# USB_SERIAL_QUAD.net
KiCad netlist of a schematic drawn in Altium Designer
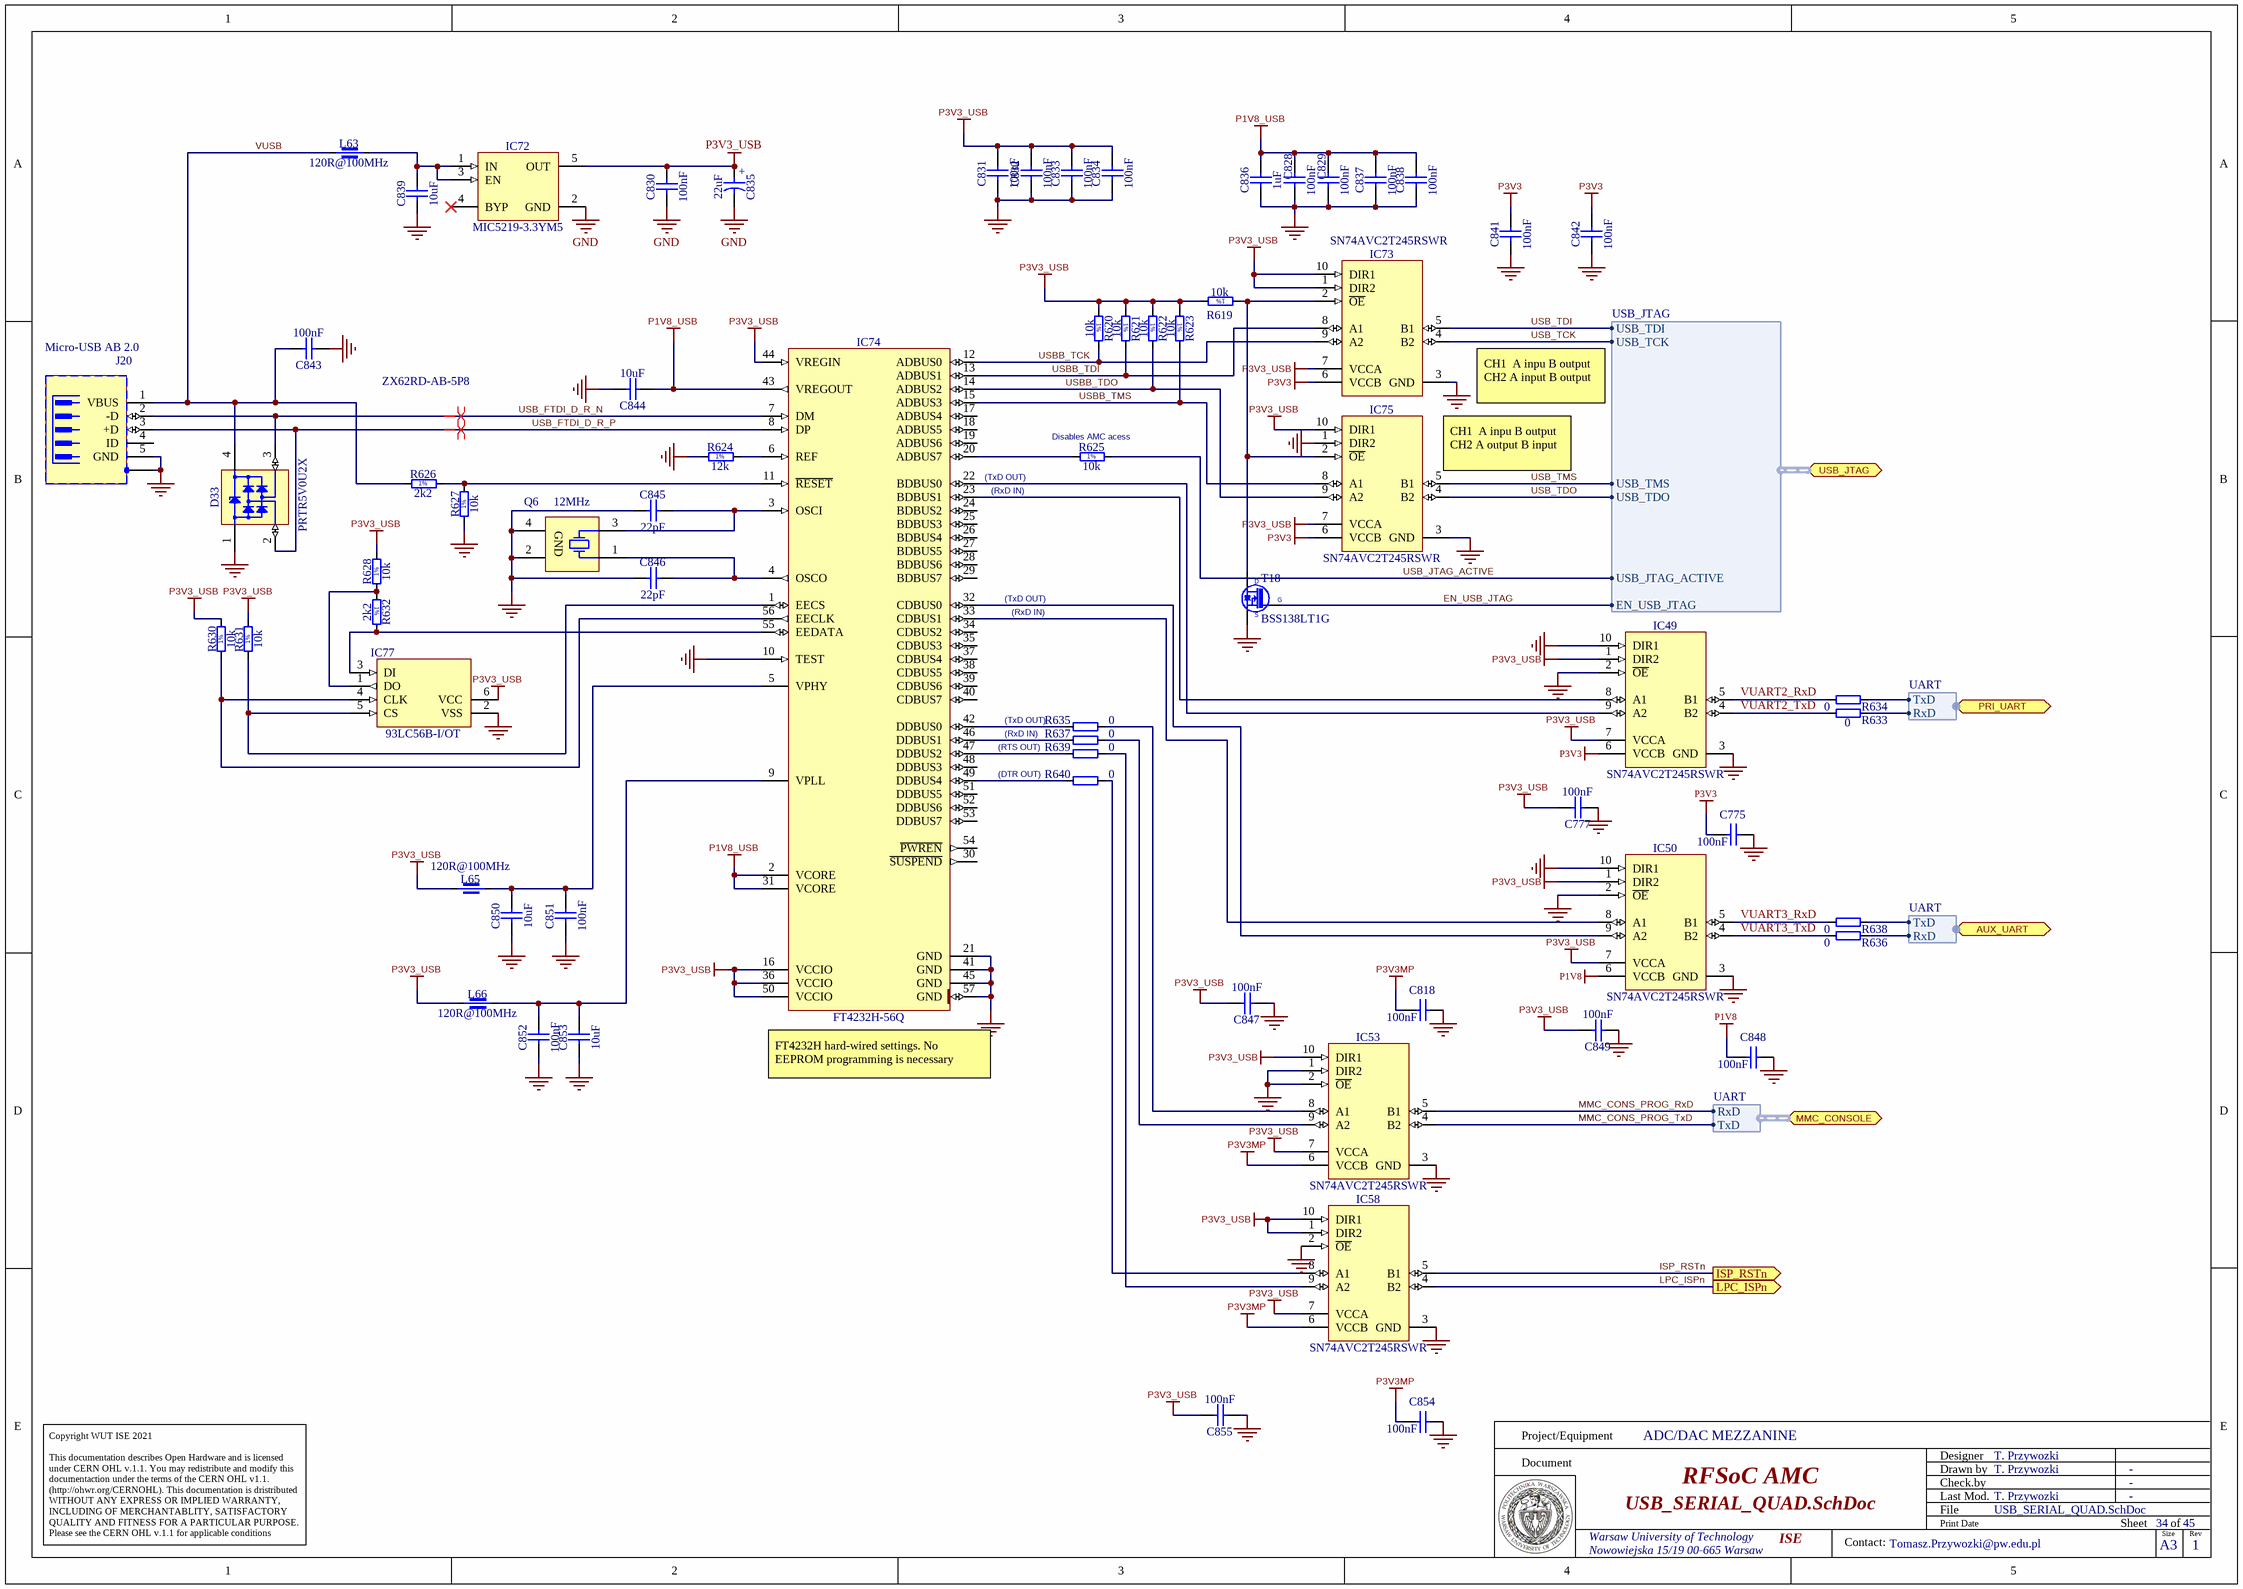
[diagram p0: USB_SERIAL_QUAD.SchDoc]

(export (version "E")
  (design (tool "Eeschema 10.0.6"))
  (components
    (comp (ref "C775")
      (value "100nF")
      (footprint "CAPC0603X33N")
      (description "Non-polarised capacitor")
      (fields
        (field (name "MANUFACTURER PART NUMBER") "CC0201_100NF_6.3V_10%_X5R")
        (field (name "MANUFACTURER") "GENERIC")
        (field (name "AUTHOR") "CERN DEM JLC")
      )
      (libsource (lib "Capacitors") (part "Capacitor - non polarized"))
    )
    (comp (ref "C777")
      (value "100nF")
      (footprint "CAPC0603X33N")
      (description "Non-polarised capacitor")
      (fields
        (field (name "MANUFACTURER PART NUMBER") "CC0201_100NF_6.3V_10%_X5R")
        (field (name "MANUFACTURER") "GENERIC")
        (field (name "AUTHOR") "CERN DEM JLC")
      )
      (libsource (lib "Capacitors") (part "Capacitor - non polarized"))
    )
    (comp (ref "C818")
      (value "100nF")
      (footprint "CAPC0603X33N")
      (description "Non-polarised capacitor")
      (fields
        (field (name "MANUFACTURER PART NUMBER") "CC0201_100NF_6.3V_10%_X5R")
        (field (name "MANUFACTURER") "GENERIC")
        (field (name "AUTHOR") "CERN DEM JLC")
      )
      (libsource (lib "Capacitors") (part "Capacitor - non polarized"))
    )
    (comp (ref "C828")
      (value "100nF")
      (footprint "CAPC0603X33N")
      (description "Non-polarised capacitor")
      (fields
        (field (name "MANUFACTURER PART NUMBER") "CC0201_100NF_6.3V_10%_X5R")
        (field (name "MANUFACTURER") "GENERIC")
        (field (name "AUTHOR") "CERN DEM JLC")
      )
      (libsource (lib "Capacitors") (part "Capacitor - non polarized"))
    )
    (comp (ref "C829")
      (value "100nF")
      (footprint "CAPC0603X33N")
      (description "Non-polarised capacitor")
      (fields
        (field (name "MANUFACTURER PART NUMBER") "CC0201_100NF_6.3V_10%_X5R")
        (field (name "MANUFACTURER") "GENERIC")
        (field (name "AUTHOR") "CERN DEM JLC")
      )
      (libsource (lib "Capacitors") (part "Capacitor - non polarized"))
    )
    (comp (ref "C830")
      (value "100nF")
      (footprint "CAPC0603X33N")
      (description "Non-polarised capacitor")
      (fields
        (field (name "PART NUMBER") "CC0201_100NF_6.3V_10%_X5R")
        (field (name "VOLTAGE") "6.3V")
        (field (name "AUTHOR") "CERN DEM JLC")
      )
      (libsource (lib "Capacitors") (part "Capacitor - non polarized"))
    )
    (comp (ref "C831")
      (value "100nF")
      (footprint "CAPC0603X33N")
      (description "Non-polarised capacitor")
      (fields
        (field (name "MANUFACTURER PART NUMBER") "CC0201_100NF_6.3V_10%_X5R")
        (field (name "MANUFACTURER") "GENERIC")
        (field (name "AUTHOR") "CERN DEM JLC")
      )
      (libsource (lib "Capacitors") (part "Capacitor - non polarized"))
    )
    (comp (ref "C832")
      (value "100nF")
      (footprint "CAPC0603X33N")
      (description "Non-polarised capacitor")
      (fields
        (field (name "MANUFACTURER PART NUMBER") "CC0201_100NF_6.3V_10%_X5R")
        (field (name "MANUFACTURER") "GENERIC")
        (field (name "AUTHOR") "CERN DEM JLC")
      )
      (libsource (lib "Capacitors") (part "Capacitor - non polarized"))
    )
    (comp (ref "C833")
      (value "100nF")
      (footprint "CAPC0603X33N")
      (description "Non-polarised capacitor")
      (fields
        (field (name "MANUFACTURER PART NUMBER") "CC0201_100NF_6.3V_10%_X5R")
        (field (name "MANUFACTURER") "GENERIC")
        (field (name "AUTHOR") "CERN DEM JLC")
      )
      (libsource (lib "Capacitors") (part "Capacitor - non polarized"))
    )
    (comp (ref "C834")
      (value "100nF")
      (footprint "CAPC0603X33N")
      (description "Non-polarised capacitor")
      (fields
        (field (name "MANUFACTURER PART NUMBER") "CC0201_100NF_6.3V_10%_X5R")
        (field (name "MANUFACTURER") "GENERIC")
        (field (name "AUTHOR") "CERN DEM JLC")
      )
      (libsource (lib "Capacitors") (part "Capacitor - non polarized"))
    )
    (comp (ref "C835")
      (value "22uF")
      (footprint "CAPMP3216X180N")
      (description "Polarised capacitor")
      (fields
        (field (name "MANUFACTURER PART NUMBER") "CTE3216-18_22UF_6.3V_10%_LESR0900")
        (field (name "MANUFACTURER") "GENERIC")
        (field (name "AUTHOR") "CERN DEM JLC")
      )
      (libsource (lib "Capacitors") (part "Capacitor - polarized"))
    )
    (comp (ref "C836")
      (value "1uF")
      (footprint "CAPC1005X55N")
      (description "Non-polarised capacitor")
      (fields
        (field (name "MANUFACTURER PART NUMBER") "CC0402_1UF_16V_10%_X5R")
        (field (name "MANUFACTURER") "GENERIC")
        (field (name "AUTHOR") "CERN DEM JLC")
      )
      (libsource (lib "Capacitors") (part "Capacitor - non polarized"))
    )
    (comp (ref "C837")
      (value "100nF")
      (footprint "CAPC0603X33N")
      (description "Non-polarised capacitor")
      (fields
        (field (name "MANUFACTURER PART NUMBER") "CC0201_100NF_6.3V_10%_X5R")
        (field (name "MANUFACTURER") "GENERIC")
        (field (name "AUTHOR") "CERN DEM JLC")
      )
      (libsource (lib "Capacitors") (part "Capacitor - non polarized"))
    )
    (comp (ref "C838")
      (value "100nF")
      (footprint "CAPC0603X33N")
      (description "Non-polarised capacitor")
      (fields
        (field (name "MANUFACTURER PART NUMBER") "CC0201_100NF_6.3V_10%_X5R")
        (field (name "MANUFACTURER") "GENERIC")
        (field (name "AUTHOR") "CERN DEM JLC")
      )
      (libsource (lib "Capacitors") (part "Capacitor - non polarized"))
    )
    (comp (ref "C839")
      (value "10uF")
      (footprint "CAPC1608X87N")
      (description "Non-polarised capacitor")
      (fields
        (field (name "MANUFACTURER PART NUMBER") "CC0603_10uF_6.3V_20%_X5R")
        (field (name "MANUFACTURER") "GENERIC")
        (field (name "AUTHOR") "CERN DEM JLC")
      )
      (libsource (lib "Capacitors") (part "Capacitor - non polarized"))
    )
    (comp (ref "C841")
      (value "100nF")
      (footprint "CAPC0603X33N")
      (description "Non-polarised capacitor")
      (fields
        (field (name "MANUFACTURER PART NUMBER") "CC0201_100NF_6.3V_10%_X5R")
        (field (name "MANUFACTURER") "GENERIC")
        (field (name "AUTHOR") "CERN DEM JLC")
      )
      (libsource (lib "Capacitors") (part "Capacitor - non polarized"))
    )
    (comp (ref "C842")
      (value "100nF")
      (footprint "CAPC0603X33N")
      (description "Non-polarised capacitor")
      (fields
        (field (name "MANUFACTURER PART NUMBER") "CC0201_100NF_6.3V_10%_X5R")
        (field (name "MANUFACTURER") "GENERIC")
        (field (name "AUTHOR") "CERN DEM JLC")
      )
      (libsource (lib "Capacitors") (part "Capacitor - non polarized"))
    )
    (comp (ref "C843")
      (value "100nF")
      (footprint "CAPC0603X33N")
      (description "Non-polarised capacitor")
      (fields
        (field (name "MANUFACTURER PART NUMBER") "CC0201_100NF_6.3V_10%_X5R")
        (field (name "MANUFACTURER") "GENERIC")
        (field (name "AUTHOR") "CERN DEM JLC")
      )
      (libsource (lib "Capacitors") (part "Capacitor - non polarized"))
    )
    (comp (ref "C844")
      (value "10uF")
      (footprint "CAPC1608X87N")
      (description "Non-polarised capacitor")
      (fields
        (field (name "MANUFACTURER PART NUMBER") "CC0603_10uF_6.3V_20%_X5R")
        (field (name "MANUFACTURER") "GENERIC")
        (field (name "AUTHOR") "CERN DEM JLC")
      )
      (libsource (lib "Capacitors") (part "Capacitor - non polarized"))
    )
    (comp (ref "C845")
      (value "22pF")
      (footprint "CAPC1005X55N")
      (description "Non-polarised capacitor")
      (fields
        (field (name "MANUFACTURER PART NUMBER") "CC0402_22PF_50V_5%_C0G")
        (field (name "MANUFACTURER") "GENERIC")
        (field (name "AUTHOR") "CERN DEM JLC")
      )
      (libsource (lib "Capacitors") (part "Capacitor - non polarized"))
    )
    (comp (ref "C846")
      (value "22pF")
      (footprint "CAPC1005X55N")
      (description "Non-polarised capacitor")
      (fields
        (field (name "MANUFACTURER PART NUMBER") "CC0402_22PF_50V_5%_C0G")
        (field (name "MANUFACTURER") "GENERIC")
        (field (name "AUTHOR") "CERN DEM JLC")
      )
      (libsource (lib "Capacitors") (part "Capacitor - non polarized"))
    )
    (comp (ref "C847")
      (value "100nF")
      (footprint "CAPC0603X33N")
      (description "Non-polarised capacitor")
      (fields
        (field (name "MANUFACTURER PART NUMBER") "CC0201_100NF_6.3V_10%_X5R")
        (field (name "MANUFACTURER") "GENERIC")
        (field (name "AUTHOR") "CERN DEM JLC")
      )
      (libsource (lib "Capacitors") (part "Capacitor - non polarized"))
    )
    (comp (ref "C848")
      (value "100nF")
      (footprint "CAPC0603X33N")
      (description "Non-polarised capacitor")
      (fields
        (field (name "MANUFACTURER PART NUMBER") "CC0201_100NF_6.3V_10%_X5R")
        (field (name "MANUFACTURER") "GENERIC")
        (field (name "AUTHOR") "CERN DEM JLC")
      )
      (libsource (lib "Capacitors") (part "Capacitor - non polarized"))
    )
    (comp (ref "C849")
      (value "100nF")
      (footprint "CAPC0603X33N")
      (description "Non-polarised capacitor")
      (fields
        (field (name "MANUFACTURER PART NUMBER") "CC0201_100NF_6.3V_10%_X5R")
        (field (name "MANUFACTURER") "GENERIC")
        (field (name "AUTHOR") "CERN DEM JLC")
      )
      (libsource (lib "Capacitors") (part "Capacitor - non polarized"))
    )
    (comp (ref "C850")
      (value "10uF")
      (footprint "CAPC1608X87N")
      (description "Non-polarised capacitor")
      (fields
        (field (name "MANUFACTURER PART NUMBER") "CC0603_10uF_6.3V_20%_X5R")
        (field (name "MANUFACTURER") "GENERIC")
        (field (name "AUTHOR") "CERN DEM JLC")
      )
      (libsource (lib "Capacitors") (part "Capacitor - non polarized"))
    )
    (comp (ref "C851")
      (value "100nF")
      (footprint "CAPC0603X33N")
      (description "Non-polarised capacitor")
      (fields
        (field (name "MANUFACTURER PART NUMBER") "CC0201_100NF_6.3V_10%_X5R")
        (field (name "MANUFACTURER") "GENERIC")
        (field (name "AUTHOR") "CERN DEM JLC")
      )
      (libsource (lib "Capacitors") (part "Capacitor - non polarized"))
    )
    (comp (ref "C852")
      (value "100nF")
      (footprint "CAPC0603X33N")
      (description "Non-polarised capacitor")
      (fields
        (field (name "MANUFACTURER PART NUMBER") "CC0201_100NF_6.3V_10%_X5R")
        (field (name "MANUFACTURER") "GENERIC")
        (field (name "AUTHOR") "CERN DEM JLC")
      )
      (libsource (lib "Capacitors") (part "Capacitor - non polarized"))
    )
    (comp (ref "C853")
      (value "10uF")
      (footprint "CAPC1608X87N")
      (description "Non-polarised capacitor")
      (fields
        (field (name "MANUFACTURER PART NUMBER") "CC0603_10uF_6.3V_20%_X5R")
        (field (name "MANUFACTURER") "GENERIC")
        (field (name "AUTHOR") "CERN DEM JLC")
      )
      (libsource (lib "Capacitors") (part "Capacitor - non polarized"))
    )
    (comp (ref "C854")
      (value "100nF")
      (footprint "CAPC0603X33N")
      (description "Non-polarised capacitor")
      (fields
        (field (name "MANUFACTURER PART NUMBER") "CC0201_100NF_6.3V_10%_X5R")
        (field (name "MANUFACTURER") "GENERIC")
        (field (name "AUTHOR") "CERN DEM JLC")
      )
      (libsource (lib "Capacitors") (part "Capacitor - non polarized"))
    )
    (comp (ref "C855")
      (value "100nF")
      (footprint "CAPC0603X33N")
      (description "Non-polarised capacitor")
      (fields
        (field (name "MANUFACTURER PART NUMBER") "CC0201_100NF_6.3V_10%_X5R")
        (field (name "MANUFACTURER") "GENERIC")
        (field (name "AUTHOR") "CERN DEM JLC")
      )
      (libsource (lib "Capacitors") (part "Capacitor - non polarized"))
    )
    (comp (ref "D33")
      (value "PRTR5V0U2X")
      (footprint "SOT190P230X110-4N")
      (description "Ultra Low Capacitance Double Rail-to-Rail ESD Protection Diode")
      (fields
        (field (name "MANUFACTURER") "NXP SEMICONDUCTORS")
        (field (name "VOLTAGE") "5.5V")
        (field (name "AUTHOR") "CERN DEM JLC")
      )
      (libsource (lib "ICs And Semiconductors") (part "PRTR5V0U2X"))
    )
    (comp (ref "IC49")
      (value "SN74AVC2T245RSWR")
      (footprint "QFN40P140X180X55-10N")
      (description "Dual-Bit Dual-Supply Bus Transceiver With Configurable Voltage Translation and 3-State Outputs")
      (fields (field (name "MANUFACTURER") "TEXAS INSTRUMENTS") (field (name "AUTHOR") "CERN DEM JLC"))
      (libsource (lib "ICs And Semiconductors") (part "742T245"))
    )
    (comp (ref "IC50")
      (value "SN74AVC2T245RSWR")
      (footprint "QFN40P140X180X55-10N")
      (description "Dual-Bit Dual-Supply Bus Transceiver With Configurable Voltage Translation and 3-State Outputs")
      (fields (field (name "MANUFACTURER") "TEXAS INSTRUMENTS") (field (name "AUTHOR") "CERN DEM JLC"))
      (libsource (lib "ICs And Semiconductors") (part "742T245"))
    )
    (comp (ref "IC53")
      (value "SN74AVC2T245RSWR")
      (footprint "QFN40P140X180X55-10N")
      (description "Dual-Bit Dual-Supply Bus Transceiver With Configurable Voltage Translation and 3-State Outputs")
      (fields (field (name "MANUFACTURER") "TEXAS INSTRUMENTS") (field (name "AUTHOR") "CERN DEM JLC"))
      (libsource (lib "ICs And Semiconductors") (part "742T245"))
    )
    (comp (ref "IC58")
      (value "SN74AVC2T245RSWR")
      (footprint "QFN40P140X180X55-10N")
      (description "Dual-Bit Dual-Supply Bus Transceiver With Configurable Voltage Translation and 3-State Outputs")
      (fields (field (name "MANUFACTURER") "TEXAS INSTRUMENTS") (field (name "AUTHOR") "CERN DEM JLC"))
      (libsource (lib "ICs And Semiconductors") (part "742T245"))
    )
    (comp (ref "IC72")
      (value "MIC5219-3.3YM5")
      (footprint "SOT95P280X145-5N")
      (description "500mA Peak Output LDO Regulator")
      (fields (field (name "MANUFACTURER") "MICROCHIP TECHNOLOGY") (field (name "AUTHOR") "CERN DEM WB"))
      (libsource (lib "ICs And Semiconductors") (part "MIC5219-X.XYM5"))
    )
    (comp (ref "IC73")
      (value "SN74AVC2T245RSWR")
      (footprint "QFN40P140X180X55-10N")
      (description "Dual-Bit Dual-Supply Bus Transceiver With Configurable Voltage Translation and 3-State Outputs")
      (fields (field (name "MANUFACTURER") "TEXAS INSTRUMENTS") (field (name "AUTHOR") "CERN DEM JLC"))
      (libsource (lib "ICs And Semiconductors") (part "742T245"))
    )
    (comp (ref "IC74")
      (value "FT4232H-56Q")
      (footprint "QFN50P800X800X100-57N-S620")
      (description "Quad High Speed USB to Multipurpose UART/MPSSE IC")
      (fields
        (field (name "MANUFACTURER") "FUTURE TECHNOLOGY DEVICES INTERNATIONAL (FTDI)")
        (field (name "AUTHOR") "CERN DEM JLC")
      )
      (libsource (lib "ICs And Semiconductors") (part "FT4232H-56Q"))
    )
    (comp (ref "IC75")
      (value "SN74AVC2T245RSWR")
      (footprint "QFN40P140X180X55-10N")
      (description "Dual-Bit Dual-Supply Bus Transceiver With Configurable Voltage Translation and 3-State Outputs")
      (fields (field (name "MANUFACTURER") "TEXAS INSTRUMENTS") (field (name "AUTHOR") "CERN DEM JLC"))
      (libsource (lib "ICs And Semiconductors") (part "742T245"))
    )
    (comp (ref "IC77")
      (value "93LC56B-I/OT")
      (footprint "SOT95P270x145-6N")
      (description "2K Microwire Compatible Serial EEPROM")
      (fields (field (name "MANUFACTURER") "MICROCHIP TECHNOLOGY") (field (name "AUTHOR") "CERN DEM BC"))
      (libsource (lib "ICs And Semiconductors") (part "93LC56B-I/OT"))
    )
    (comp (ref "J20")
      (value "Micro-USB AB 2.0")
      (footprint "HIROSE_ZX62RD-AB-5P8")
      (description "5 Pin + 1 Shield USB Receptacle")
      (fields
        (field (name "MANUFACTURER PART NUMBER") "ZX62RD-AB-5P8")
        (field (name "MANUFACTURER") "HIROSE (HRS)")
        (field (name "PART NUMBER") "HIROSE_ZX62RD-AB-5P8")
        (field (name "AUTHOR") "CERN DEM JLC")
      )
      (libsource (lib "Connectors") (part "Connector USB 5 Pin + 1Shield"))
    )
    (comp (ref "L63")
      (value "120R@100MHz")
      (footprint "INDC1608X65N")
      (fields
        (field (name "MANUFACTURER PART NUMBER") "BLM18SG121TN1D")
        (field (name "MANUFACTURER") "MURATA")
        (field (name "PART NUMBER") "IND0603_MURATA_BLM18SG121TN1D")
        (field (name "AUTHOR") "CERN DEM JLC")
      )
      (libsource (lib "Inductors & Transformers") (part "Ferrite Bead"))
    )
    (comp (ref "L65")
      (value "120R@100MHz")
      (footprint "INDC1608X65N")
      (fields
        (field (name "MANUFACTURER PART NUMBER") "BLM18SG121TN1D")
        (field (name "MANUFACTURER") "MURATA")
        (field (name "PART NUMBER") "IND0603_MURATA_BLM18SG121TN1D")
        (field (name "AUTHOR") "CERN DEM JLC")
      )
      (libsource (lib "Inductors & Transformers") (part "Ferrite Bead"))
    )
    (comp (ref "L66")
      (value "120R@100MHz")
      (footprint "INDC1608X65N")
      (fields
        (field (name "MANUFACTURER PART NUMBER") "BLM18SG121TN1D")
        (field (name "MANUFACTURER") "MURATA")
        (field (name "PART NUMBER") "IND0603_MURATA_BLM18SG121TN1D")
        (field (name "AUTHOR") "CERN DEM JLC")
      )
      (libsource (lib "Inductors & Transformers") (part "Ferrite Bead"))
    )
    (comp (ref "Q6")
      (value "12MHz")
      (footprint "XTAL_TXC_7M")
      (description "Crystal 4 pins 1=XTAL Control 2=GND3=XTAL 4=GND")
      (fields
        (field (name "MANUFACTURER PART NUMBER") "7M-12.000MAAJ-T")
        (field (name "MANUFACTURER") "TXC CORPORATION")
        (field (name "AUTHOR") "CERN DEM JLC")
      )
      (libsource (lib "ICs And Semiconductors") (part "Quartz Crystal 1X 2GND 3X 4GND"))
    )
    (comp (ref "R619")
      (value "10k")
      (footprint "RESC1005X40N")
      (description "Resistor - 1%")
      (fields
        (field (name "MANUFACTURER PART NUMBER") "R0402_10K_1%_0.0625W_100PPM")
        (field (name "MANUFACTURER") "GENERIC")
        (field (name "AUTHOR") "CERN DEM JLC")
      )
      (libsource (lib "Resistors") (part "Resistor - 1%"))
    )
    (comp (ref "R620")
      (value "10k")
      (footprint "RESC1005X40N")
      (description "Resistor - 1%")
      (fields
        (field (name "MANUFACTURER PART NUMBER") "R0402_10K_1%_0.0625W_100PPM")
        (field (name "MANUFACTURER") "GENERIC")
        (field (name "AUTHOR") "CERN DEM JLC")
      )
      (libsource (lib "Resistors") (part "Resistor - 1%"))
    )
    (comp (ref "R621")
      (value "10k")
      (footprint "RESC1005X40N")
      (description "Resistor - 1%")
      (fields
        (field (name "MANUFACTURER PART NUMBER") "R0402_10K_1%_0.0625W_100PPM")
        (field (name "MANUFACTURER") "GENERIC")
        (field (name "AUTHOR") "CERN DEM JLC")
      )
      (libsource (lib "Resistors") (part "Resistor - 1%"))
    )
    (comp (ref "R622")
      (value "10k")
      (footprint "RESC1005X40N")
      (description "Resistor - 1%")
      (fields
        (field (name "MANUFACTURER PART NUMBER") "R0402_10K_1%_0.0625W_100PPM")
        (field (name "MANUFACTURER") "GENERIC")
        (field (name "AUTHOR") "CERN DEM JLC")
      )
      (libsource (lib "Resistors") (part "Resistor - 1%"))
    )
    (comp (ref "R623")
      (value "10k")
      (footprint "RESC1005X40N")
      (description "Resistor - 1%")
      (fields
        (field (name "MANUFACTURER PART NUMBER") "R0402_10K_1%_0.0625W_100PPM")
        (field (name "MANUFACTURER") "GENERIC")
        (field (name "AUTHOR") "CERN DEM JLC")
      )
      (libsource (lib "Resistors") (part "Resistor - 1%"))
    )
    (comp (ref "R624")
      (value "12k")
      (footprint "RESC1005X40N")
      (description "Resistor - 1%")
      (fields
        (field (name "MANUFACTURER PART NUMBER") "R0402_12K_1%_0.0625W_100PPM")
        (field (name "MANUFACTURER") "GENERIC")
        (field (name "AUTHOR") "CERN DEM JLC")
      )
      (libsource (lib "Resistors") (part "Resistor - 1%"))
    )
    (comp (ref "R625")
      (value "10k")
      (footprint "RESC1005X40N")
      (description "Resistor - 1%")
      (fields
        (field (name "MANUFACTURER PART NUMBER") "R0402_10K_1%_0.0625W_100PPM")
        (field (name "MANUFACTURER") "GENERIC")
        (field (name "AUTHOR") "CERN DEM JLC")
      )
      (libsource (lib "Resistors") (part "Resistor - 1%"))
    )
    (comp (ref "R626")
      (value "2k2")
      (footprint "RESC1005X40N")
      (description "Resistor - 1%")
      (fields
        (field (name "MANUFACTURER PART NUMBER") "R0402_2K2_1%_0.0625W_100PPM")
        (field (name "MANUFACTURER") "GENERIC")
        (field (name "AUTHOR") "CERN DEM JLC")
      )
      (libsource (lib "Resistors") (part "Resistor - 1%"))
    )
    (comp (ref "R627")
      (value "10k")
      (footprint "RESC1005X40N")
      (description "Resistor - 1%")
      (fields
        (field (name "MANUFACTURER PART NUMBER") "R0402_10K_1%_0.0625W_100PPM")
        (field (name "MANUFACTURER") "GENERIC")
        (field (name "AUTHOR") "CERN DEM JLC")
      )
      (libsource (lib "Resistors") (part "Resistor - 1%"))
    )
    (comp (ref "R628")
      (value "10k")
      (footprint "RESC1005X40N")
      (description "Resistor - 1%")
      (fields
        (field (name "MANUFACTURER PART NUMBER") "R0402_10K_1%_0.0625W_100PPM")
        (field (name "MANUFACTURER") "GENERIC")
        (field (name "AUTHOR") "CERN DEM JLC")
      )
      (libsource (lib "Resistors") (part "Resistor - 1%"))
    )
    (comp (ref "R630")
      (value "10k")
      (footprint "RESC1005X40N")
      (description "Resistor - 1%")
      (fields
        (field (name "MANUFACTURER PART NUMBER") "R0402_10K_1%_0.0625W_100PPM")
        (field (name "MANUFACTURER") "GENERIC")
        (field (name "AUTHOR") "CERN DEM JLC")
      )
      (libsource (lib "Resistors") (part "Resistor - 1%"))
    )
    (comp (ref "R631")
      (value "10k")
      (footprint "RESC1005X40N")
      (description "Resistor - 1%")
      (fields
        (field (name "MANUFACTURER PART NUMBER") "R0402_10K_1%_0.0625W_100PPM")
        (field (name "MANUFACTURER") "GENERIC")
        (field (name "AUTHOR") "CERN DEM JLC")
      )
      (libsource (lib "Resistors") (part "Resistor - 1%"))
    )
    (comp (ref "R632")
      (value "2k2")
      (footprint "RESC1005X40N")
      (description "Resistor - 1%")
      (fields
        (field (name "MANUFACTURER PART NUMBER") "R0402_2K2_1%_0.0625W_100PPM")
        (field (name "MANUFACTURER") "GENERIC")
        (field (name "AUTHOR") "CERN DEM JLC")
      )
      (libsource (lib "Resistors") (part "Resistor - 1%"))
    )
    (comp (ref "R633")
      (value "0")
      (footprint "RESC1005X40N")
      (description "Resistor")
      (fields
        (field (name "MANUFACTURER PART NUMBER") "R0402_0R_JUMPER")
        (field (name "MANUFACTURER") "GENERIC")
        (field (name "AUTHOR") "CERN DEM JLC")
      )
      (libsource (lib "Resistors") (part "Resistor"))
    )
    (comp (ref "R634")
      (value "0")
      (footprint "RESC1005X40N")
      (description "Resistor")
      (fields
        (field (name "MANUFACTURER PART NUMBER") "R0402_0R_JUMPER")
        (field (name "MANUFACTURER") "GENERIC")
        (field (name "AUTHOR") "CERN DEM JLC")
      )
      (libsource (lib "Resistors") (part "Resistor"))
    )
    (comp (ref "R635")
      (value "0")
      (footprint "RESC1005X40N")
      (description "Resistor")
      (fields
        (field (name "MANUFACTURER PART NUMBER") "R0402_0R_JUMPER")
        (field (name "MANUFACTURER") "GENERIC")
        (field (name "AUTHOR") "CERN DEM JLC")
      )
      (libsource (lib "Resistors") (part "Resistor"))
    )
    (comp (ref "R636")
      (value "0")
      (footprint "RESC1005X40N")
      (description "Resistor")
      (fields
        (field (name "MANUFACTURER PART NUMBER") "R0402_0R_JUMPER")
        (field (name "MANUFACTURER") "GENERIC")
        (field (name "AUTHOR") "CERN DEM JLC")
      )
      (libsource (lib "Resistors") (part "Resistor"))
    )
    (comp (ref "R637")
      (value "0")
      (footprint "RESC1005X40N")
      (description "Resistor")
      (fields
        (field (name "MANUFACTURER PART NUMBER") "R0402_0R_JUMPER")
        (field (name "MANUFACTURER") "GENERIC")
        (field (name "AUTHOR") "CERN DEM JLC")
      )
      (libsource (lib "Resistors") (part "Resistor"))
    )
    (comp (ref "R638")
      (value "0")
      (footprint "RESC1005X40N")
      (description "Resistor")
      (fields
        (field (name "MANUFACTURER PART NUMBER") "R0402_0R_JUMPER")
        (field (name "MANUFACTURER") "GENERIC")
        (field (name "AUTHOR") "CERN DEM JLC")
      )
      (libsource (lib "Resistors") (part "Resistor"))
    )
    (comp (ref "R639")
      (value "0")
      (footprint "RESC1005X40N")
      (description "Resistor")
      (fields
        (field (name "MANUFACTURER PART NUMBER") "R0402_0R_JUMPER")
        (field (name "MANUFACTURER") "GENERIC")
        (field (name "AUTHOR") "CERN DEM JLC")
      )
      (libsource (lib "Resistors") (part "Resistor"))
    )
    (comp (ref "R640")
      (value "0")
      (footprint "RESC1005X40N")
      (description "Resistor")
      (fields
        (field (name "MANUFACTURER PART NUMBER") "R0402_0R_JUMPER")
        (field (name "MANUFACTURER") "GENERIC")
        (field (name "AUTHOR") "CERN DEM JLC")
      )
      (libsource (lib "Resistors") (part "Resistor"))
    )
    (comp (ref "T18")
      (value "BSS138LT1G")
      (footprint "SOT95P240X110-3N")
      (description "N-CHANNEL MOSFET WITH DIODE")
      (fields (field (name "MANUFACTURER") "ON SEMICONDUCTOR") (field (name "AUTHOR") "CERN DEM JLC"))
      (libsource (lib "ICs And Semiconductors") (part "N-MOSFET-D 1G 2S 3D"))
    )
  )
  (nets
    (net (code "3") (name "/EN_USB_JTAG") (class "Default")
      (node (ref "T18") (pin "1") (pinfunction "G_1") (pintype "passive"))
    )
    (net (code "4") (name "/ISP_RSTn") (class "Default")
      (node (ref "IC58") (pin "5") (pinfunction "B1_5") (pintype "bidirectional"))
    )
    (net (code "5") (name "/LPC_ISPn") (class "Default")
      (node (ref "IC58") (pin "4") (pinfunction "B2_4") (pintype "bidirectional"))
    )
    (net (code "6") (name "/MMC_CONS_PROG_RxD") (class "Default")
      (node (ref "IC53") (pin "5") (pinfunction "B1_5") (pintype "bidirectional"))
    )
    (net (code "7") (name "/MMC_CONS_PROG_TxD") (class "Default")
      (node (ref "IC53") (pin "4") (pinfunction "B2_4") (pintype "bidirectional"))
    )
    (net (code "8") (name "/USBB_TCK") (class "Default")
      (node (ref "IC73") (pin "9") (pinfunction "A2_9") (pintype "bidirectional"))
      (node (ref "IC74") (pin "12") (pinfunction "ADBUS0_12") (pintype "bidirectional"))
      (node (ref "R620") (pin "2") (pinfunction "2_2") (pintype "passive"))
    )
    (net (code "9") (name "/USBB_TDI") (class "Default")
      (node (ref "IC73") (pin "8") (pinfunction "A1_8") (pintype "bidirectional"))
      (node (ref "IC74") (pin "13") (pinfunction "ADBUS1_13") (pintype "bidirectional"))
      (node (ref "R621") (pin "2") (pinfunction "2_2") (pintype "passive"))
    )
    (net (code "10") (name "/USBB_TDO") (class "Default")
      (node (ref "IC74") (pin "14") (pinfunction "ADBUS2_14") (pintype "bidirectional"))
      (node (ref "IC75") (pin "9") (pinfunction "A2_9") (pintype "bidirectional"))
      (node (ref "R622") (pin "2") (pinfunction "2_2") (pintype "passive"))
    )
    (net (code "11") (name "/USBB_TMS") (class "Default")
      (node (ref "IC74") (pin "15") (pinfunction "ADBUS3_15") (pintype "bidirectional"))
      (node (ref "IC75") (pin "8") (pinfunction "A1_8") (pintype "bidirectional"))
      (node (ref "R623") (pin "2") (pinfunction "2_2") (pintype "passive"))
    )
    (net (code "12") (name "/USB_FTDI_D_R_N") (class "Default")
      (node (ref "D33") (pin "3") (pinfunction "I/O2_3") (pintype "bidirectional"))
      (node (ref "IC74") (pin "7") (pinfunction "DM_7") (pintype "input"))
      (node (ref "J20") (pin "2") (pinfunction "-D_2") (pintype "bidirectional"))
    )
    (net (code "13") (name "/USB_FTDI_D_R_P") (class "Default")
      (node (ref "D33") (pin "2") (pinfunction "I/O1_2") (pintype "bidirectional"))
      (node (ref "IC74") (pin "8") (pinfunction "DP_8") (pintype "input"))
      (node (ref "J20") (pin "3") (pinfunction "+D_3") (pintype "bidirectional"))
    )
    (net (code "14") (name "/USB_JTAG_ACTIVE") (class "Default")
      (node (ref "R625") (pin "2") (pinfunction "2_2") (pintype "passive"))
    )
    (net (code "15") (name "/USB_TCK") (class "Default")
      (node (ref "IC73") (pin "4") (pinfunction "B2_4") (pintype "bidirectional"))
    )
    (net (code "16") (name "/USB_TDI") (class "Default")
      (node (ref "IC73") (pin "5") (pinfunction "B1_5") (pintype "bidirectional"))
    )
    (net (code "17") (name "/USB_TDO") (class "Default")
      (node (ref "IC75") (pin "4") (pinfunction "B2_4") (pintype "bidirectional"))
    )
    (net (code "18") (name "/USB_TMS") (class "Default")
      (node (ref "IC75") (pin "5") (pinfunction "B1_5") (pintype "bidirectional"))
    )
    (net (code "19") (name "/VUART2_RxD") (class "Default")
      (node (ref "IC49") (pin "5") (pinfunction "B1_5") (pintype "bidirectional"))
      (node (ref "R634") (pin "2") (pinfunction "2_2") (pintype "passive"))
    )
    (net (code "20") (name "/VUART2_TxD") (class "Default")
      (node (ref "IC49") (pin "4") (pinfunction "B2_4") (pintype "bidirectional"))
      (node (ref "R633") (pin "2") (pinfunction "2_2") (pintype "passive"))
    )
    (net (code "21") (name "/VUART3_RxD") (class "Default")
      (node (ref "IC50") (pin "5") (pinfunction "B1_5") (pintype "bidirectional"))
      (node (ref "R638") (pin "2") (pinfunction "2_2") (pintype "passive"))
    )
    (net (code "22") (name "/VUART3_TxD") (class "Default")
      (node (ref "IC50") (pin "4") (pinfunction "B2_4") (pintype "bidirectional"))
      (node (ref "R636") (pin "2") (pinfunction "2_2") (pintype "passive"))
    )
    (net (code "23") (name "/VUSB") (class "Default")
      (node (ref "C843") (pin "2") (pinfunction "2_2") (pintype "passive"))
      (node (ref "D33") (pin "4") (pinfunction "VCC_4") (pintype "power_in"))
      (node (ref "J20") (pin "1") (pinfunction "VBUS_1") (pintype "power_in"))
      (node (ref "L63") (pin "1") (pinfunction "1_1") (pintype "passive"))
      (node (ref "R626") (pin "1") (pinfunction "1_1") (pintype "passive"))
    )
    (net (code "26") (name "GND") (class "Default")
      (node (ref "C775") (pin "1") (pinfunction "1_1") (pintype "passive"))
      (node (ref "C777") (pin "1") (pinfunction "1_1") (pintype "passive"))
      (node (ref "C818") (pin "1") (pinfunction "1_1") (pintype "passive"))
      (node (ref "C828") (pin "1") (pinfunction "1_1") (pintype "passive"))
      (node (ref "C829") (pin "1") (pinfunction "1_1") (pintype "passive"))
      (node (ref "C830") (pin "1") (pinfunction "1_1") (pintype "passive"))
      (node (ref "C831") (pin "1") (pinfunction "1_1") (pintype "passive"))
      (node (ref "C832") (pin "1") (pinfunction "1_1") (pintype "passive"))
      (node (ref "C833") (pin "1") (pinfunction "1_1") (pintype "passive"))
      (node (ref "C834") (pin "1") (pinfunction "1_1") (pintype "passive"))
      (node (ref "C835") (pin "2") (pinfunction "2_2") (pintype "passive"))
      (node (ref "C836") (pin "2") (pinfunction "2_2") (pintype "passive"))
      (node (ref "C837") (pin "1") (pinfunction "1_1") (pintype "passive"))
      (node (ref "C838") (pin "1") (pinfunction "1_1") (pintype "passive"))
      (node (ref "C839") (pin "1") (pinfunction "1_1") (pintype "passive"))
      (node (ref "C841") (pin "1") (pinfunction "1_1") (pintype "passive"))
      (node (ref "C842") (pin "1") (pinfunction "1_1") (pintype "passive"))
      (node (ref "C843") (pin "1") (pinfunction "1_1") (pintype "passive"))
      (node (ref "C844") (pin "2") (pinfunction "2_2") (pintype "passive"))
      (node (ref "C845") (pin "1") (pinfunction "1_1") (pintype "passive"))
      (node (ref "C846") (pin "1") (pinfunction "1_1") (pintype "passive"))
      (node (ref "C847") (pin "1") (pinfunction "1_1") (pintype "passive"))
      (node (ref "C848") (pin "1") (pinfunction "1_1") (pintype "passive"))
      (node (ref "C849") (pin "1") (pinfunction "1_1") (pintype "passive"))
      (node (ref "C850") (pin "1") (pinfunction "1_1") (pintype "passive"))
      (node (ref "C851") (pin "1") (pinfunction "1_1") (pintype "passive"))
      (node (ref "C852") (pin "1") (pinfunction "1_1") (pintype "passive"))
      (node (ref "C853") (pin "1") (pinfunction "1_1") (pintype "passive"))
      (node (ref "C854") (pin "1") (pinfunction "1_1") (pintype "passive"))
      (node (ref "C855") (pin "1") (pinfunction "1_1") (pintype "passive"))
      (node (ref "D33") (pin "1") (pinfunction "GND_1") (pintype "power_in"))
      (node (ref "IC49") (pin "10") (pinfunction "DIR1_10") (pintype "input"))
      (node (ref "IC49") (pin "2") (pinfunction "~{OE}_2") (pintype "input"))
      (node (ref "IC49") (pin "3") (pinfunction "GND_3") (pintype "power_in"))
      (node (ref "IC50") (pin "10") (pinfunction "DIR1_10") (pintype "input"))
      (node (ref "IC50") (pin "2") (pinfunction "~{OE}_2") (pintype "input"))
      (node (ref "IC50") (pin "3") (pinfunction "GND_3") (pintype "power_in"))
      (node (ref "IC53") (pin "1") (pinfunction "DIR2_1") (pintype "input"))
      (node (ref "IC53") (pin "2") (pinfunction "~{OE}_2") (pintype "input"))
      (node (ref "IC53") (pin "3") (pinfunction "GND_3") (pintype "power_in"))
      (node (ref "IC58") (pin "2") (pinfunction "~{OE}_2") (pintype "input"))
      (node (ref "IC58") (pin "3") (pinfunction "GND_3") (pintype "power_in"))
      (node (ref "IC72") (pin "2") (pinfunction "GND_2") (pintype "power_in"))
      (node (ref "IC73") (pin "3") (pinfunction "GND_3") (pintype "power_in"))
      (node (ref "IC74") (pin "10") (pinfunction "TEST_10") (pintype "input"))
      (node (ref "IC74") (pin "21") (pinfunction "GND_21") (pintype "power_in"))
      (node (ref "IC74") (pin "41") (pinfunction "GND_41") (pintype "power_in"))
      (node (ref "IC74") (pin "45") (pinfunction "GND_45") (pintype "power_in"))
      (node (ref "IC74") (pin "57") (pinfunction "GND_57") (pintype "bidirectional"))
      (node (ref "IC75") (pin "1") (pinfunction "DIR2_1") (pintype "input"))
      (node (ref "IC75") (pin "3") (pinfunction "GND_3") (pintype "power_in"))
      (node (ref "IC77") (pin "2") (pinfunction "VSS_2") (pintype "power_in"))
      (node (ref "J20") (pin "5") (pinfunction "GND_5") (pintype "power_in"))
      (node (ref "J20") (pin "6") (pinfunction "SH_6") (pintype "power_in"))
      (node (ref "Q6") (pin "2") (pinfunction "GND_2") (pintype "power_in"))
      (node (ref "Q6") (pin "4") (pinfunction "GND_4") (pintype "power_in"))
      (node (ref "R624") (pin "1") (pinfunction "1_1") (pintype "passive"))
      (node (ref "R627") (pin "1") (pinfunction "1_1") (pintype "passive"))
      (node (ref "T18") (pin "2") (pinfunction "S_2") (pintype "passive"))
    )
    (net (code "27") (name "Net-(IC49-A1)") (class "Default")
      (node (ref "IC49") (pin "8") (pinfunction "A1_8") (pintype "bidirectional"))
      (node (ref "IC74") (pin "23") (pinfunction "BDBUS1_23") (pintype "bidirectional"))
    )
    (net (code "28") (name "Net-(IC49-A2)") (class "Default")
      (node (ref "IC49") (pin "9") (pinfunction "A2_9") (pintype "bidirectional"))
      (node (ref "IC74") (pin "22") (pinfunction "BDBUS0_22") (pintype "bidirectional"))
    )
    (net (code "29") (name "Net-(IC50-A1)") (class "Default")
      (node (ref "IC50") (pin "8") (pinfunction "A1_8") (pintype "bidirectional"))
      (node (ref "IC74") (pin "33") (pinfunction "CDBUS1_33") (pintype "bidirectional"))
    )
    (net (code "30") (name "Net-(IC50-A2)") (class "Default")
      (node (ref "IC50") (pin "9") (pinfunction "A2_9") (pintype "bidirectional"))
      (node (ref "IC74") (pin "32") (pinfunction "CDBUS0_32") (pintype "bidirectional"))
    )
    (net (code "31") (name "Net-(IC53-A1)") (class "Default")
      (node (ref "IC53") (pin "8") (pinfunction "A1_8") (pintype "bidirectional"))
      (node (ref "R635") (pin "2") (pinfunction "2_2") (pintype "passive"))
    )
    (net (code "32") (name "Net-(IC53-A2)") (class "Default")
      (node (ref "IC53") (pin "9") (pinfunction "A2_9") (pintype "bidirectional"))
      (node (ref "R637") (pin "2") (pinfunction "2_2") (pintype "passive"))
    )
    (net (code "33") (name "Net-(IC58-A1)") (class "Default")
      (node (ref "IC58") (pin "8") (pinfunction "A1_8") (pintype "bidirectional"))
      (node (ref "R640") (pin "2") (pinfunction "2_2") (pintype "passive"))
    )
    (net (code "34") (name "Net-(IC58-A2)") (class "Default")
      (node (ref "IC58") (pin "9") (pinfunction "A2_9") (pintype "bidirectional"))
      (node (ref "R639") (pin "2") (pinfunction "2_2") (pintype "passive"))
    )
    (net (code "35") (name "Net-(IC72-EN)") (class "Default")
      (node (ref "C839") (pin "2") (pinfunction "2_2") (pintype "passive"))
      (node (ref "IC72") (pin "1") (pinfunction "IN_1") (pintype "input"))
      (node (ref "IC72") (pin "3") (pinfunction "EN_3") (pintype "input"))
      (node (ref "L63") (pin "2") (pinfunction "2_2") (pintype "passive"))
    )
    (net (code "36") (name "Net-(IC73-~{OE})") (class "Default")
      (node (ref "IC73") (pin "2") (pinfunction "~{OE}_2") (pintype "input"))
      (node (ref "IC75") (pin "2") (pinfunction "~{OE}_2") (pintype "input"))
      (node (ref "R619") (pin "1") (pinfunction "1_1") (pintype "passive"))
      (node (ref "T18") (pin "3") (pinfunction "D_3") (pintype "passive"))
    )
    (net (code "37") (name "Net-(IC74-ADBUS7)") (class "Default")
      (node (ref "IC74") (pin "20") (pinfunction "ADBUS7_20") (pintype "bidirectional"))
      (node (ref "R625") (pin "1") (pinfunction "1_1") (pintype "passive"))
    )
    (net (code "38") (name "Net-(IC74-DDBUS0)") (class "Default")
      (node (ref "IC74") (pin "42") (pinfunction "DDBUS0_42") (pintype "bidirectional"))
      (node (ref "R635") (pin "1") (pinfunction "1_1") (pintype "passive"))
    )
    (net (code "39") (name "Net-(IC74-DDBUS1)") (class "Default")
      (node (ref "IC74") (pin "46") (pinfunction "DDBUS1_46") (pintype "bidirectional"))
      (node (ref "R637") (pin "1") (pinfunction "1_1") (pintype "passive"))
    )
    (net (code "40") (name "Net-(IC74-DDBUS2)") (class "Default")
      (node (ref "IC74") (pin "47") (pinfunction "DDBUS2_47") (pintype "bidirectional"))
      (node (ref "R639") (pin "1") (pinfunction "1_1") (pintype "passive"))
    )
    (net (code "41") (name "Net-(IC74-DDBUS4)") (class "Default")
      (node (ref "IC74") (pin "49") (pinfunction "DDBUS4_49") (pintype "bidirectional"))
      (node (ref "R640") (pin "1") (pinfunction "1_1") (pintype "passive"))
    )
    (net (code "42") (name "Net-(IC74-EECLK)") (class "Default")
      (node (ref "IC74") (pin "56") (pinfunction "EECLK_56") (pintype "output"))
      (node (ref "IC77") (pin "4") (pinfunction "CLK_4") (pintype "input"))
      (node (ref "R630") (pin "1") (pinfunction "1_1") (pintype "passive"))
    )
    (net (code "43") (name "Net-(IC74-EECS)") (class "Default")
      (node (ref "IC74") (pin "1") (pinfunction "EECS_1") (pintype "bidirectional"))
      (node (ref "IC77") (pin "5") (pinfunction "CS_5") (pintype "input"))
      (node (ref "R631") (pin "1") (pinfunction "1_1") (pintype "passive"))
    )
    (net (code "44") (name "Net-(IC74-EEDATA)") (class "Default")
      (node (ref "IC74") (pin "55") (pinfunction "EEDATA_55") (pintype "bidirectional"))
      (node (ref "IC77") (pin "3") (pinfunction "DI_3") (pintype "input"))
      (node (ref "R632") (pin "2") (pinfunction "2_2") (pintype "passive"))
    )
    (net (code "45") (name "Net-(IC74-OSCI)") (class "Default")
      (node (ref "C845") (pin "2") (pinfunction "2_2") (pintype "passive"))
      (node (ref "IC74") (pin "3") (pinfunction "OSCI_3") (pintype "input"))
      (node (ref "Q6") (pin "3") (pinfunction "X_3") (pintype "passive"))
    )
    (net (code "46") (name "Net-(IC74-OSCO)") (class "Default")
      (node (ref "C846") (pin "2") (pinfunction "2_2") (pintype "passive"))
      (node (ref "IC74") (pin "4") (pinfunction "OSCO_4") (pintype "output"))
      (node (ref "Q6") (pin "1") (pinfunction "X_1") (pintype "passive"))
    )
    (net (code "47") (name "Net-(IC74-REF)") (class "Default")
      (node (ref "IC74") (pin "6") (pinfunction "REF_6") (pintype "input"))
      (node (ref "R624") (pin "2") (pinfunction "2_2") (pintype "passive"))
    )
    (net (code "48") (name "Net-(IC74-VPHY)") (class "Default")
      (node (ref "C850") (pin "2") (pinfunction "2_2") (pintype "passive"))
      (node (ref "C851") (pin "2") (pinfunction "2_2") (pintype "passive"))
      (node (ref "IC74") (pin "5") (pinfunction "VPHY_5") (pintype "power_in"))
      (node (ref "L65") (pin "2") (pinfunction "2_2") (pintype "passive"))
    )
    (net (code "49") (name "Net-(IC74-VPLL)") (class "Default")
      (node (ref "C852") (pin "2") (pinfunction "2_2") (pintype "passive"))
      (node (ref "C853") (pin "2") (pinfunction "2_2") (pintype "passive"))
      (node (ref "IC74") (pin "9") (pinfunction "VPLL_9") (pintype "power_in"))
      (node (ref "L66") (pin "2") (pinfunction "2_2") (pintype "passive"))
    )
    (net (code "50") (name "Net-(IC74-~{RESET})") (class "Default")
      (node (ref "IC74") (pin "11") (pinfunction "~{RESET}_11") (pintype "input"))
      (node (ref "R626") (pin "2") (pinfunction "2_2") (pintype "passive"))
      (node (ref "R627") (pin "2") (pinfunction "2_2") (pintype "passive"))
    )
    (net (code "51") (name "Net-(IC77-DO)") (class "Default")
      (node (ref "IC77") (pin "1") (pinfunction "DO_1") (pintype "output"))
      (node (ref "R628") (pin "1") (pinfunction "1_1") (pintype "passive"))
      (node (ref "R632") (pin "1") (pinfunction "1_1") (pintype "passive"))
    )
    (net (code "52") (name "P1V8") (class "Default")
      (node (ref "C848") (pin "2") (pinfunction "2_2") (pintype "passive"))
      (node (ref "IC50") (pin "6") (pinfunction "VCCB_6") (pintype "power_in"))
    )
    (net (code "53") (name "P1V8_USB") (class "Default")
      (node (ref "C828") (pin "2") (pinfunction "2_2") (pintype "passive"))
      (node (ref "C829") (pin "2") (pinfunction "2_2") (pintype "passive"))
      (node (ref "C836") (pin "1") (pinfunction "1_1") (pintype "passive"))
      (node (ref "C837") (pin "2") (pinfunction "2_2") (pintype "passive"))
      (node (ref "C838") (pin "2") (pinfunction "2_2") (pintype "passive"))
      (node (ref "C844") (pin "1") (pinfunction "1_1") (pintype "passive"))
      (node (ref "IC74") (pin "2") (pinfunction "VCORE_2") (pintype "power_in"))
      (node (ref "IC74") (pin "31") (pinfunction "VCORE_31") (pintype "power_in"))
      (node (ref "IC74") (pin "43") (pinfunction "VREGOUT_43") (pintype "output"))
    )
    (net (code "54") (name "P3V3") (class "Default")
      (node (ref "C775") (pin "2") (pinfunction "2_2") (pintype "passive"))
      (node (ref "C841") (pin "2") (pinfunction "2_2") (pintype "passive"))
      (node (ref "C842") (pin "2") (pinfunction "2_2") (pintype "passive"))
      (node (ref "IC49") (pin "6") (pinfunction "VCCB_6") (pintype "power_in"))
      (node (ref "IC73") (pin "6") (pinfunction "VCCB_6") (pintype "power_in"))
      (node (ref "IC75") (pin "6") (pinfunction "VCCB_6") (pintype "power_in"))
    )
    (net (code "55") (name "P3V3MP") (class "Default")
      (node (ref "C818") (pin "2") (pinfunction "2_2") (pintype "passive"))
      (node (ref "C854") (pin "2") (pinfunction "2_2") (pintype "passive"))
      (node (ref "IC53") (pin "6") (pinfunction "VCCB_6") (pintype "power_in"))
      (node (ref "IC58") (pin "6") (pinfunction "VCCB_6") (pintype "power_in"))
    )
    (net (code "56") (name "P3V3_USB") (class "Default")
      (node (ref "C777") (pin "2") (pinfunction "2_2") (pintype "passive"))
      (node (ref "C830") (pin "2") (pinfunction "2_2") (pintype "passive"))
      (node (ref "C831") (pin "2") (pinfunction "2_2") (pintype "passive"))
      (node (ref "C832") (pin "2") (pinfunction "2_2") (pintype "passive"))
      (node (ref "C833") (pin "2") (pinfunction "2_2") (pintype "passive"))
      (node (ref "C834") (pin "2") (pinfunction "2_2") (pintype "passive"))
      (node (ref "C835") (pin "1") (pinfunction "1_1") (pintype "passive"))
      (node (ref "C847") (pin "2") (pinfunction "2_2") (pintype "passive"))
      (node (ref "C849") (pin "2") (pinfunction "2_2") (pintype "passive"))
      (node (ref "C855") (pin "2") (pinfunction "2_2") (pintype "passive"))
      (node (ref "IC49") (pin "1") (pinfunction "DIR2_1") (pintype "input"))
      (node (ref "IC49") (pin "7") (pinfunction "VCCA_7") (pintype "power_in"))
      (node (ref "IC50") (pin "1") (pinfunction "DIR2_1") (pintype "input"))
      (node (ref "IC50") (pin "7") (pinfunction "VCCA_7") (pintype "power_in"))
      (node (ref "IC53") (pin "10") (pinfunction "DIR1_10") (pintype "input"))
      (node (ref "IC53") (pin "7") (pinfunction "VCCA_7") (pintype "power_in"))
      (node (ref "IC58") (pin "1") (pinfunction "DIR2_1") (pintype "input"))
      (node (ref "IC58") (pin "10") (pinfunction "DIR1_10") (pintype "input"))
      (node (ref "IC58") (pin "7") (pinfunction "VCCA_7") (pintype "power_in"))
      (node (ref "IC72") (pin "5") (pinfunction "OUT_5") (pintype "power_in"))
      (node (ref "IC73") (pin "1") (pinfunction "DIR2_1") (pintype "input"))
      (node (ref "IC73") (pin "10") (pinfunction "DIR1_10") (pintype "input"))
      (node (ref "IC73") (pin "7") (pinfunction "VCCA_7") (pintype "power_in"))
      (node (ref "IC74") (pin "16") (pinfunction "VCCIO_16") (pintype "power_in"))
      (node (ref "IC74") (pin "36") (pinfunction "VCCIO_36") (pintype "power_in"))
      (node (ref "IC74") (pin "44") (pinfunction "VREGIN_44") (pintype "input"))
      (node (ref "IC74") (pin "50") (pinfunction "VCCIO_50") (pintype "power_in"))
      (node (ref "IC75") (pin "10") (pinfunction "DIR1_10") (pintype "input"))
      (node (ref "IC75") (pin "7") (pinfunction "VCCA_7") (pintype "power_in"))
      (node (ref "IC77") (pin "6") (pinfunction "VCC_6") (pintype "power_in"))
      (node (ref "L65") (pin "1") (pinfunction "1_1") (pintype "passive"))
      (node (ref "L66") (pin "1") (pinfunction "1_1") (pintype "passive"))
      (node (ref "R619") (pin "2") (pinfunction "2_2") (pintype "passive"))
      (node (ref "R620") (pin "1") (pinfunction "1_1") (pintype "passive"))
      (node (ref "R621") (pin "1") (pinfunction "1_1") (pintype "passive"))
      (node (ref "R622") (pin "1") (pinfunction "1_1") (pintype "passive"))
      (node (ref "R623") (pin "1") (pinfunction "1_1") (pintype "passive"))
      (node (ref "R628") (pin "2") (pinfunction "2_2") (pintype "passive"))
      (node (ref "R630") (pin "2") (pinfunction "2_2") (pintype "passive"))
      (node (ref "R631") (pin "2") (pinfunction "2_2") (pintype "passive"))
    )
    (net (code "57") (name "unconnected-(IC72-BYP-Pad4)") (class "Default")
      (node (ref "IC72") (pin "4") (pinfunction "BYP_4") (pintype "passive+no_connect"))
    )
    (net (code "58") (name "unconnected-(IC74-ADBUS4-Pad17)") (class "Default")
      (node (ref "IC74") (pin "17") (pinfunction "ADBUS4_17") (pintype "bidirectional"))
    )
    (net (code "59") (name "unconnected-(IC74-ADBUS5-Pad18)") (class "Default")
      (node (ref "IC74") (pin "18") (pinfunction "ADBUS5_18") (pintype "bidirectional"))
    )
    (net (code "60") (name "unconnected-(IC74-ADBUS6-Pad19)") (class "Default")
      (node (ref "IC74") (pin "19") (pinfunction "ADBUS6_19") (pintype "bidirectional"))
    )
    (net (code "61") (name "unconnected-(IC74-BDBUS2-Pad24)") (class "Default")
      (node (ref "IC74") (pin "24") (pinfunction "BDBUS2_24") (pintype "bidirectional"))
    )
    (net (code "62") (name "unconnected-(IC74-BDBUS3-Pad25)") (class "Default")
      (node (ref "IC74") (pin "25") (pinfunction "BDBUS3_25") (pintype "bidirectional"))
    )
    (net (code "63") (name "unconnected-(IC74-BDBUS4-Pad26)") (class "Default")
      (node (ref "IC74") (pin "26") (pinfunction "BDBUS4_26") (pintype "bidirectional"))
    )
    (net (code "64") (name "unconnected-(IC74-BDBUS5-Pad27)") (class "Default")
      (node (ref "IC74") (pin "27") (pinfunction "BDBUS5_27") (pintype "bidirectional"))
    )
    (net (code "65") (name "unconnected-(IC74-BDBUS6-Pad28)") (class "Default")
      (node (ref "IC74") (pin "28") (pinfunction "BDBUS6_28") (pintype "bidirectional"))
    )
    (net (code "66") (name "unconnected-(IC74-BDBUS7-Pad29)") (class "Default")
      (node (ref "IC74") (pin "29") (pinfunction "BDBUS7_29") (pintype "bidirectional"))
    )
    (net (code "67") (name "unconnected-(IC74-CDBUS2-Pad34)") (class "Default")
      (node (ref "IC74") (pin "34") (pinfunction "CDBUS2_34") (pintype "bidirectional"))
    )
    (net (code "68") (name "unconnected-(IC74-CDBUS3-Pad35)") (class "Default")
      (node (ref "IC74") (pin "35") (pinfunction "CDBUS3_35") (pintype "bidirectional"))
    )
    (net (code "69") (name "unconnected-(IC74-CDBUS4-Pad37)") (class "Default")
      (node (ref "IC74") (pin "37") (pinfunction "CDBUS4_37") (pintype "bidirectional"))
    )
    (net (code "70") (name "unconnected-(IC74-CDBUS5-Pad38)") (class "Default")
      (node (ref "IC74") (pin "38") (pinfunction "CDBUS5_38") (pintype "bidirectional"))
    )
    (net (code "71") (name "unconnected-(IC74-CDBUS6-Pad39)") (class "Default")
      (node (ref "IC74") (pin "39") (pinfunction "CDBUS6_39") (pintype "bidirectional"))
    )
    (net (code "72") (name "unconnected-(IC74-CDBUS7-Pad40)") (class "Default")
      (node (ref "IC74") (pin "40") (pinfunction "CDBUS7_40") (pintype "bidirectional"))
    )
    (net (code "73") (name "unconnected-(IC74-DDBUS3-Pad48)") (class "Default")
      (node (ref "IC74") (pin "48") (pinfunction "DDBUS3_48") (pintype "bidirectional"))
    )
    (net (code "74") (name "unconnected-(IC74-DDBUS5-Pad51)") (class "Default")
      (node (ref "IC74") (pin "51") (pinfunction "DDBUS5_51") (pintype "bidirectional"))
    )
    (net (code "75") (name "unconnected-(IC74-DDBUS6-Pad52)") (class "Default")
      (node (ref "IC74") (pin "52") (pinfunction "DDBUS6_52") (pintype "bidirectional"))
    )
    (net (code "76") (name "unconnected-(IC74-DDBUS7-Pad53)") (class "Default")
      (node (ref "IC74") (pin "53") (pinfunction "DDBUS7_53") (pintype "bidirectional"))
    )
    (net (code "77") (name "unconnected-(IC74-~{PWREN}-Pad54)") (class "Default")
      (node (ref "IC74") (pin "54") (pinfunction "~{PWREN}_54") (pintype "output"))
    )
    (net (code "78") (name "unconnected-(IC74-~{SUSPEND}-Pad30)") (class "Default")
      (node (ref "IC74") (pin "30") (pinfunction "~{SUSPEND}_30") (pintype "output"))
    )
    (net (code "79") (name "unconnected-(J20-ID-Pad4)") (class "Default")
      (node (ref "J20") (pin "4") (pinfunction "ID_4") (pintype "passive"))
    )
    (net (code "80") (name "unconnected-(R633-Pad1)") (class "Default")
      (node (ref "R633") (pin "1") (pinfunction "1_1") (pintype "passive"))
    )
    (net (code "81") (name "unconnected-(R634-Pad1)") (class "Default")
      (node (ref "R634") (pin "1") (pinfunction "1_1") (pintype "passive"))
    )
    (net (code "82") (name "unconnected-(R636-Pad1)") (class "Default")
      (node (ref "R636") (pin "1") (pinfunction "1_1") (pintype "passive"))
    )
    (net (code "83") (name "unconnected-(R638-Pad1)") (class "Default")
      (node (ref "R638") (pin "1") (pinfunction "1_1") (pintype "passive"))
    )
  )
)
